# Roland.net
KiCad netlist of a schematic drawn in EAGLE
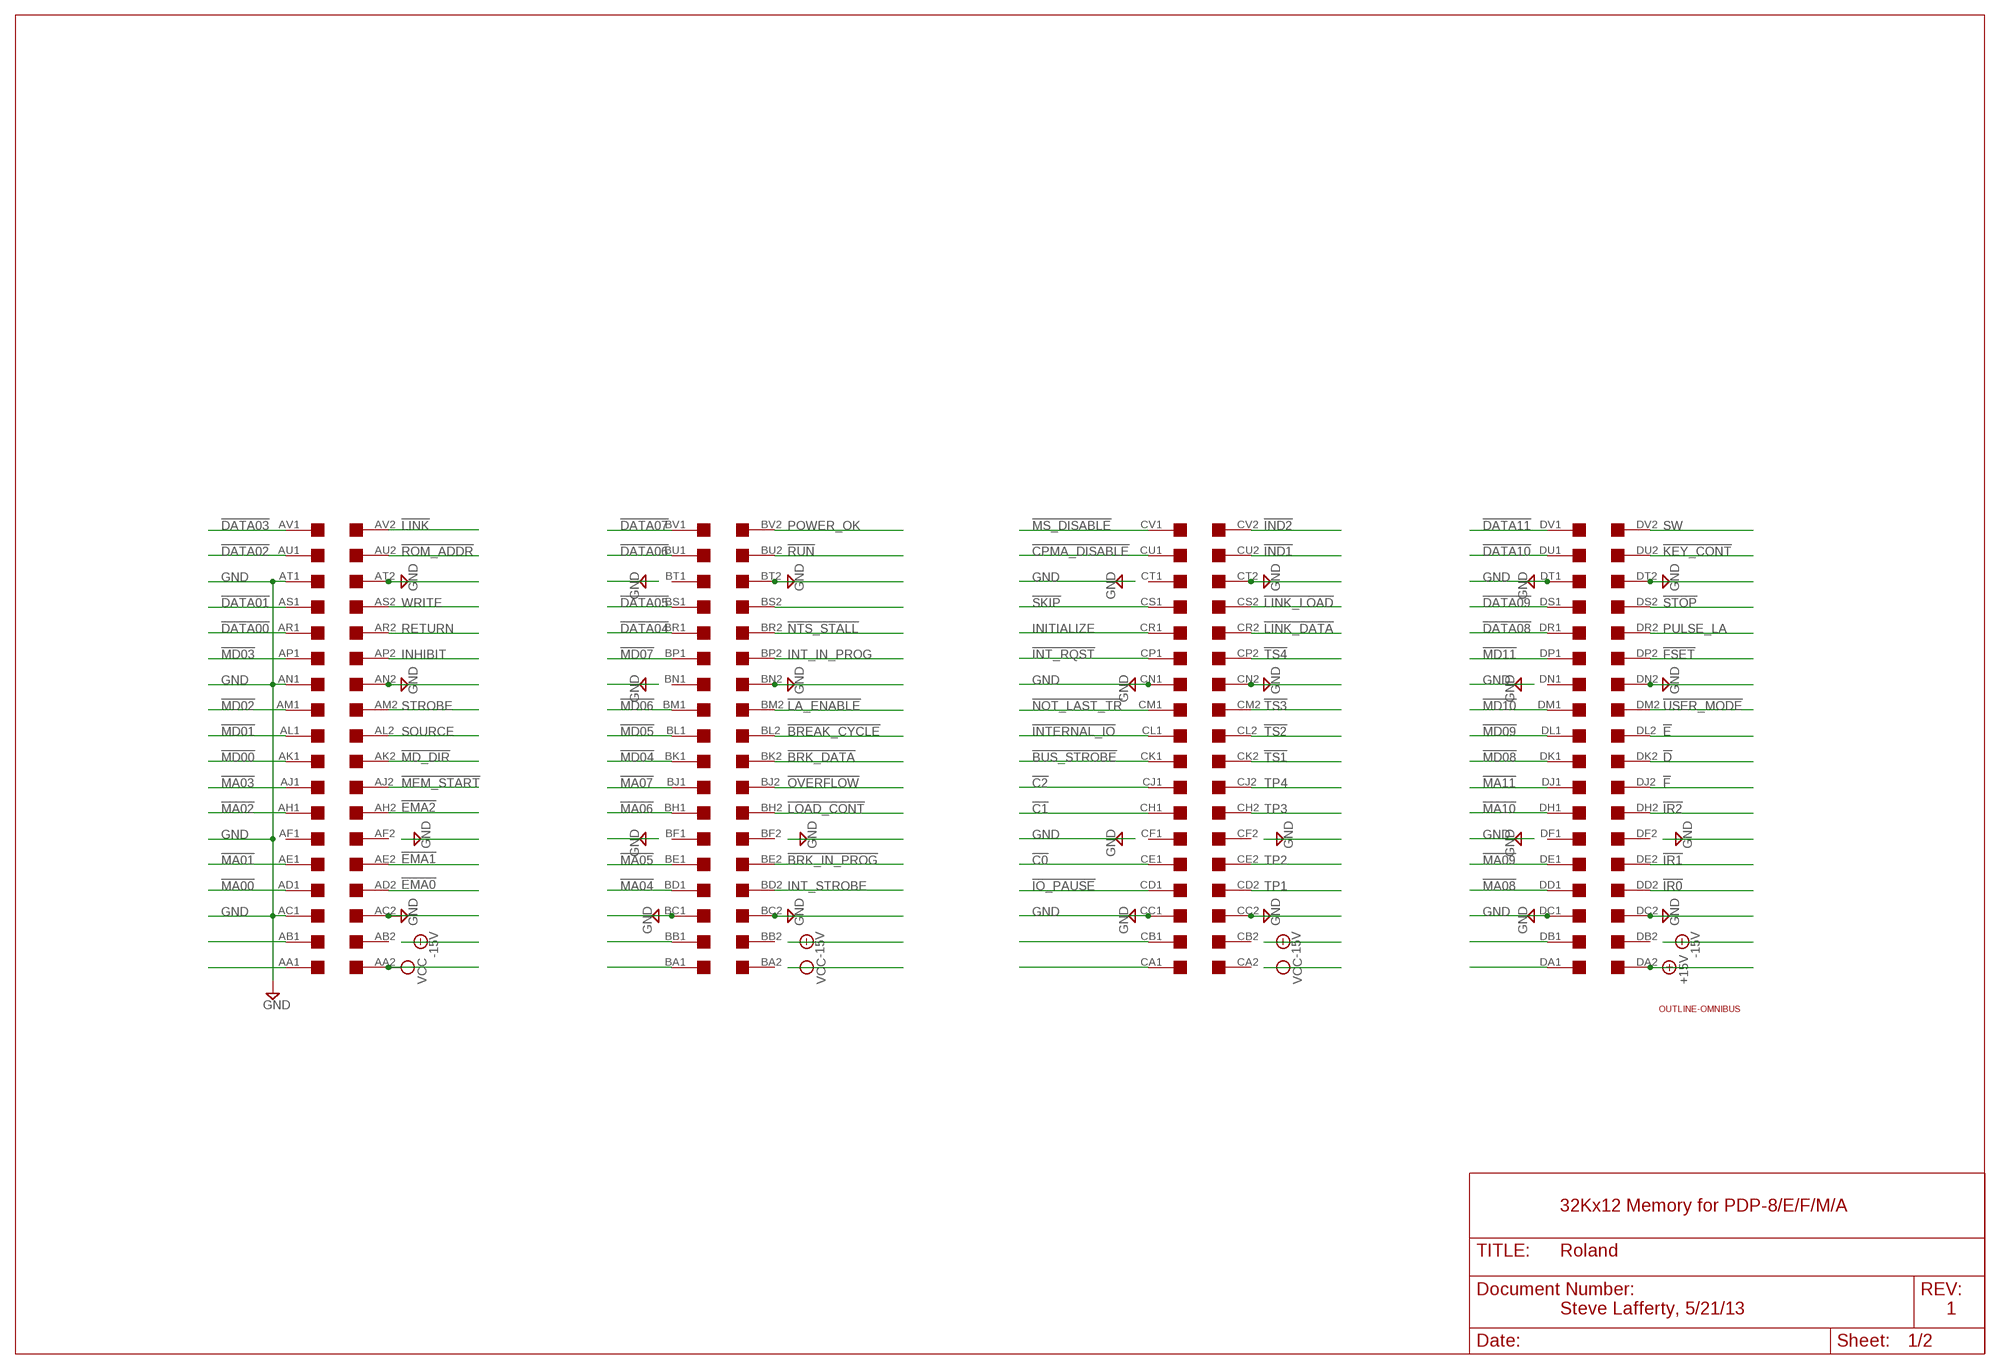
[diagram p0: schematic, sheet 1]
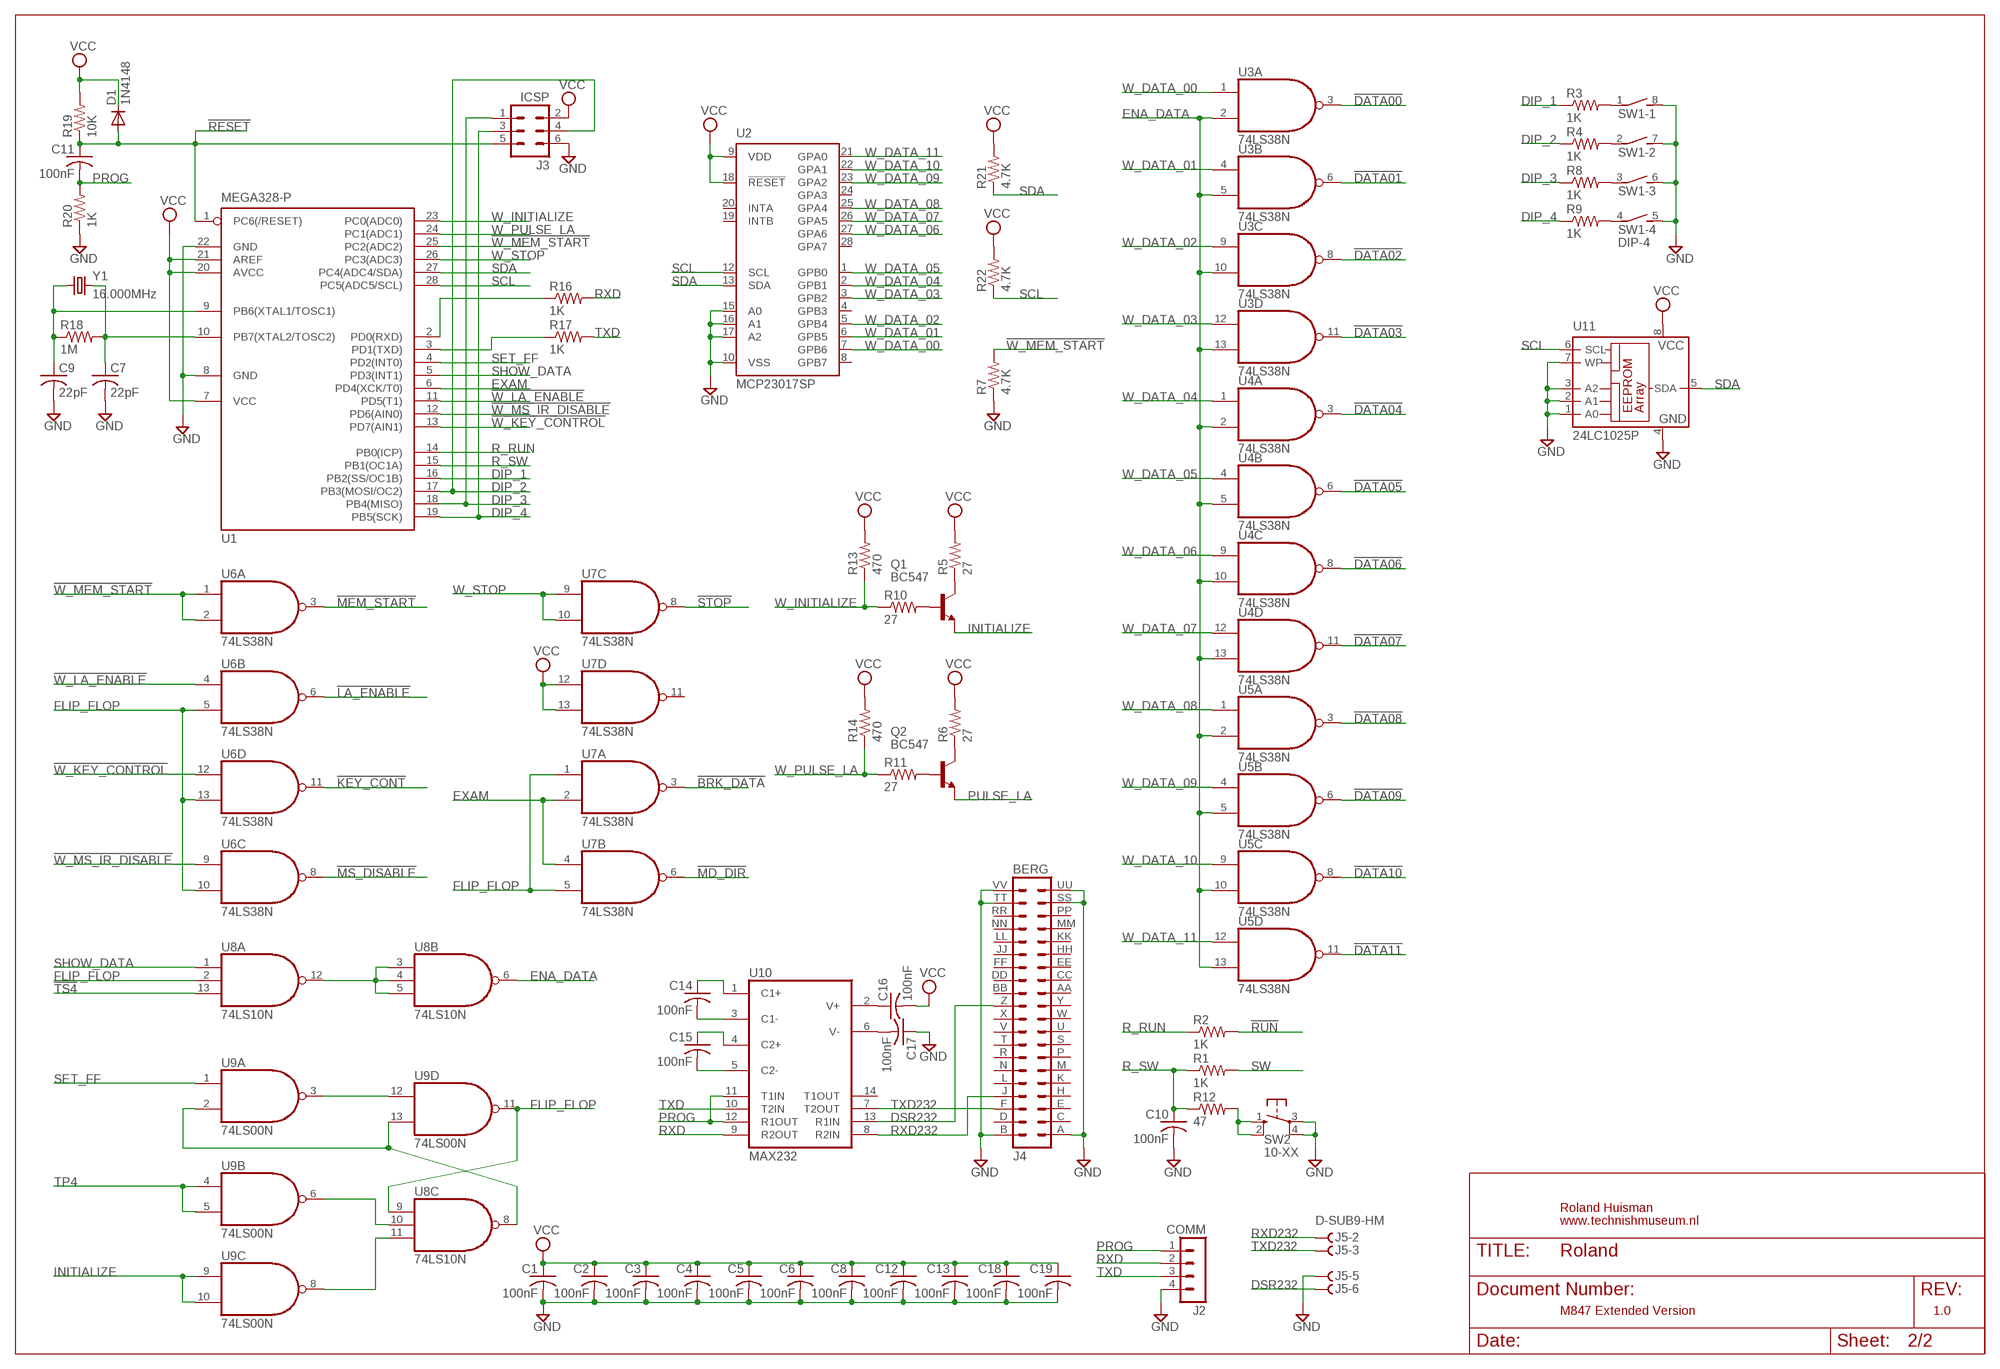
[diagram p1: schematic, sheet 2]

(export (version "E")
  (design (tool "Eeschema 10.0.6"))
  (components
    (comp (ref "J1")
      (value "EDGE")
      (footprint "eagle-import:EDGE-CON8")
      (libsource (lib "eagle-import") (part "QUAD"))
    )
    (comp (ref "U$1")
      (value "OUTLINE-OMNIBUS")
      (footprint "eagle-import:OMNIBUS")
      (libsource (lib "eagle-import") (part "OUTLINE-OMNIBUS"))
    )
    (comp (ref "C1")
      (value "100nF")
      (footprint "eagle-import:C050-025X075")
      (libsource (lib "eagle-import") (part "C-US050-025X075"))
    )
    (comp (ref "C2")
      (value "100nF")
      (footprint "eagle-import:C050-025X075")
      (libsource (lib "eagle-import") (part "C-US050-025X075"))
    )
    (comp (ref "C3")
      (value "100nF")
      (footprint "eagle-import:C050-025X075")
      (libsource (lib "eagle-import") (part "C-US050-025X075"))
    )
    (comp (ref "C4")
      (value "100nF")
      (footprint "eagle-import:C050-025X075")
      (libsource (lib "eagle-import") (part "C-US050-025X075"))
    )
    (comp (ref "C5")
      (value "100nF")
      (footprint "eagle-import:C050-025X075")
      (libsource (lib "eagle-import") (part "C-US050-025X075"))
    )
    (comp (ref "C6")
      (value "100nF")
      (footprint "eagle-import:C050-025X075")
      (libsource (lib "eagle-import") (part "C-US050-025X075"))
    )
    (comp (ref "C7")
      (value "22pF")
      (footprint "eagle-import:C050-025X075")
      (libsource (lib "eagle-import") (part "C-US050-025X075"))
    )
    (comp (ref "C8")
      (value "100nF")
      (footprint "eagle-import:C050-025X075")
      (libsource (lib "eagle-import") (part "C-US050-025X075"))
    )
    (comp (ref "C9")
      (value "22pF")
      (footprint "eagle-import:C050-025X075")
      (libsource (lib "eagle-import") (part "C-US050-025X075"))
    )
    (comp (ref "C10")
      (value "100nF")
      (footprint "eagle-import:C050-025X075")
      (libsource (lib "eagle-import") (part "C-US050-025X075"))
    )
    (comp (ref "C11")
      (value "100nF")
      (footprint "eagle-import:C050-025X075")
      (libsource (lib "eagle-import") (part "C-US050-025X075"))
    )
    (comp (ref "C12")
      (value "100nF")
      (footprint "eagle-import:C050-025X075")
      (libsource (lib "eagle-import") (part "C-US050-025X075"))
    )
    (comp (ref "C13")
      (value "100nF")
      (footprint "eagle-import:C050-025X075")
      (libsource (lib "eagle-import") (part "C-US050-025X075"))
    )
    (comp (ref "C14")
      (value "100nF")
      (footprint "eagle-import:C050-025X075")
      (libsource (lib "eagle-import") (part "C-US050-025X075"))
    )
    (comp (ref "C15")
      (value "100nF")
      (footprint "eagle-import:C050-025X075")
      (libsource (lib "eagle-import") (part "C-US050-025X075"))
    )
    (comp (ref "C16")
      (value "100nF")
      (footprint "eagle-import:C050-025X075")
      (libsource (lib "eagle-import") (part "C-US050-025X075"))
    )
    (comp (ref "C17")
      (value "100nF")
      (footprint "eagle-import:C050-025X075")
      (libsource (lib "eagle-import") (part "C-US050-025X075"))
    )
    (comp (ref "C18")
      (value "100nF")
      (footprint "eagle-import:C050-025X075")
      (libsource (lib "eagle-import") (part "C-US050-025X075"))
    )
    (comp (ref "C19")
      (value "100nF")
      (footprint "eagle-import:C050-025X075")
      (libsource (lib "eagle-import") (part "C-US050-025X075"))
    )
    (comp (ref "D1")
      (value "1N4148")
      (footprint "eagle-import:DO35-10")
      (libsource (lib "eagle-import") (part "1N4148DO35-10"))
    )
    (comp (ref "J2")
      (value "COMM")
      (footprint "eagle-import:MA04-1")
      (libsource (lib "eagle-import") (part "MA04-1"))
    )
    (comp (ref "J3")
      (value "ICSP")
      (footprint "eagle-import:MA03-2")
      (libsource (lib "eagle-import") (part "MA03-2"))
    )
    (comp (ref "J4")
      (value "BERG")
      (footprint "eagle-import:DEC40PINH")
      (libsource (lib "eagle-import") (part "DEC40PINH"))
    )
    (comp (ref "J5")
      (value "D-SUB9-HM")
      (footprint "eagle-import:H5M09RA")
      (libsource (lib "eagle-import") (part "D-SUB9-H5M09RA"))
    )
    (comp (ref "Q1")
      (value "BC547")
      (footprint "eagle-import:TO5")
      (libsource (lib "eagle-import") (part "-NPN-TO5"))
    )
    (comp (ref "Q2")
      (value "BC547")
      (footprint "eagle-import:TO5")
      (libsource (lib "eagle-import") (part "-NPN-TO5"))
    )
    (comp (ref "R1")
      (value "1K")
      (footprint "eagle-import:0207_15")
      (libsource (lib "eagle-import") (part "R-US_0207/15"))
    )
    (comp (ref "R2")
      (value "1K")
      (footprint "eagle-import:0207_15")
      (libsource (lib "eagle-import") (part "R-US_0207/15"))
    )
    (comp (ref "R3")
      (value "1K")
      (footprint "eagle-import:0207_15")
      (libsource (lib "eagle-import") (part "R-US_0207/15"))
    )
    (comp (ref "R4")
      (value "1K")
      (footprint "eagle-import:0207_15")
      (libsource (lib "eagle-import") (part "R-US_0207/15"))
    )
    (comp (ref "R5")
      (value "27")
      (footprint "eagle-import:0207_15")
      (libsource (lib "eagle-import") (part "R-US_0207/15"))
    )
    (comp (ref "R6")
      (value "27")
      (footprint "eagle-import:0207_15")
      (libsource (lib "eagle-import") (part "R-US_0207/15"))
    )
    (comp (ref "R7")
      (value "4.7K")
      (footprint "eagle-import:0207_15")
      (libsource (lib "eagle-import") (part "R-US_0207/15"))
    )
    (comp (ref "R8")
      (value "1K")
      (footprint "eagle-import:0207_15")
      (libsource (lib "eagle-import") (part "R-US_0207/15"))
    )
    (comp (ref "R9")
      (value "1K")
      (footprint "eagle-import:0207_15")
      (libsource (lib "eagle-import") (part "R-US_0207/15"))
    )
    (comp (ref "R10")
      (value "27")
      (footprint "eagle-import:0207_15")
      (libsource (lib "eagle-import") (part "R-US_0207/15"))
    )
    (comp (ref "R11")
      (value "27")
      (footprint "eagle-import:0207_15")
      (libsource (lib "eagle-import") (part "R-US_0207/15"))
    )
    (comp (ref "R12")
      (value "47")
      (footprint "eagle-import:0207_15")
      (libsource (lib "eagle-import") (part "R-US_0207/15"))
    )
    (comp (ref "R13")
      (value "470")
      (footprint "eagle-import:0207_15")
      (libsource (lib "eagle-import") (part "R-US_0207/15"))
    )
    (comp (ref "R14")
      (value "470")
      (footprint "eagle-import:0207_15")
      (libsource (lib "eagle-import") (part "R-US_0207/15"))
    )
    (comp (ref "R16")
      (value "1K")
      (footprint "eagle-import:0207_15")
      (libsource (lib "eagle-import") (part "R-US_0207/15"))
    )
    (comp (ref "R17")
      (value "1K")
      (footprint "eagle-import:0207_15")
      (libsource (lib "eagle-import") (part "R-US_0207/15"))
    )
    (comp (ref "R18")
      (value "1M")
      (footprint "eagle-import:0207_15")
      (libsource (lib "eagle-import") (part "R-US_0207/15"))
    )
    (comp (ref "R19")
      (value "10K")
      (footprint "eagle-import:0207_15")
      (libsource (lib "eagle-import") (part "R-US_0207/15"))
    )
    (comp (ref "R20")
      (value "1K")
      (footprint "eagle-import:0207_15")
      (libsource (lib "eagle-import") (part "R-US_0207/15"))
    )
    (comp (ref "R21")
      (value "4.7K")
      (footprint "eagle-import:0207_15")
      (libsource (lib "eagle-import") (part "R-US_0207/15"))
    )
    (comp (ref "R22")
      (value "4.7K")
      (footprint "eagle-import:0207_15")
      (libsource (lib "eagle-import") (part "R-US_0207/15"))
    )
    (comp (ref "SW1")
      (value "DIP-4")
      (footprint "eagle-import:DIP04S")
      (libsource (lib "eagle-import") (part "DIP04S"))
    )
    (comp (ref "SW2")
      (value "10-XX")
      (footprint "eagle-import:B3F-10XX")
      (fields (field (name "MPN") "B3F-1000"))
      (libsource (lib "eagle-import") (part "10-XX"))
    )
    (comp (ref "U1")
      (value "MEGA328-P")
      (footprint "eagle-import:DIL28-3")
      (libsource (lib "eagle-import") (part "MEGA8-P"))
    )
    (comp (ref "U2")
      (value "MCP23017SP")
      (footprint "eagle-import:DIL28-3")
      (fields (field (name "MF") "MICROCHIP") (field (name "MPN") "MCP23017-E/SP"))
      (libsource (lib "eagle-import") (part "MCP23017SP"))
    )
    (comp (ref "U3")
      (value "74LS38N")
      (footprint "eagle-import:DIL14")
      (libsource (lib "eagle-import") (part "7438NLS"))
    )
    (comp (ref "U4")
      (value "74LS38N")
      (footprint "eagle-import:DIL14")
      (libsource (lib "eagle-import") (part "7438NLS"))
    )
    (comp (ref "U5")
      (value "74LS38N")
      (footprint "eagle-import:DIL14")
      (libsource (lib "eagle-import") (part "7438NLS"))
    )
    (comp (ref "U6")
      (value "74LS38N")
      (footprint "eagle-import:DIL14")
      (libsource (lib "eagle-import") (part "7438NLS"))
    )
    (comp (ref "U7")
      (value "74LS38N")
      (footprint "eagle-import:DIL14")
      (libsource (lib "eagle-import") (part "7438NLS"))
    )
    (comp (ref "U8")
      (value "74LS10N")
      (footprint "eagle-import:DIL14")
      (libsource (lib "eagle-import") (part "7410NLS"))
    )
    (comp (ref "U9")
      (value "74LS00N")
      (footprint "eagle-import:DIL14")
      (libsource (lib "eagle-import") (part "7400NLS"))
    )
    (comp (ref "U10")
      (value "MAX232")
      (footprint "eagle-import:DIL16")
      (fields (field (name "MF") "MAXIM") (field (name "MPN") "MAX232ACPE+"))
      (libsource (lib "eagle-import") (part "MAX232"))
    )
    (comp (ref "U11")
      (value "24LC1025P")
      (footprint "eagle-import:DIL8")
      (fields (field (name "MF") "MICROCHIP") (field (name "MPN") "24LC025-I/P"))
      (libsource (lib "eagle-import") (part "24PLC025"))
    )
    (comp (ref "Y1")
      (value "16.000MHz")
      (footprint "eagle-import:HC49U-H")
      (libsource (lib "eagle-import") (part "CRYSTALHC49U-H"))
    )
  )
  (nets
    (net (code "1") (name "+15V") (class "Default")
      (node (ref "J1") (pin "DA2") (pinfunction "1_DA2") (pintype "bidirectional"))
    )
    (net (code "3") (name "DIP_1") (class "Default")
      (node (ref "R3") (pin "1") (pinfunction "1_1") (pintype "passive"))
      (node (ref "U1") (pin "16") (pinfunction "PB2(SS/OC1B)_16") (pintype "bidirectional"))
    )
    (net (code "4") (name "DIP_2") (class "Default")
      (node (ref "J3") (pin "4") (pinfunction "4_4") (pintype "passive"))
      (node (ref "R4") (pin "1") (pinfunction "1_1") (pintype "passive"))
      (node (ref "U1") (pin "17") (pinfunction "PB3(MOSI/OC2)_17") (pintype "bidirectional"))
    )
    (net (code "5") (name "DIP_3") (class "Default")
      (node (ref "J3") (pin "1") (pinfunction "1_1") (pintype "passive"))
      (node (ref "R8") (pin "1") (pinfunction "1_1") (pintype "passive"))
      (node (ref "U1") (pin "18") (pinfunction "PB4(MISO)_18") (pintype "bidirectional"))
    )
    (net (code "6") (name "DIP_4") (class "Default")
      (node (ref "J3") (pin "3") (pinfunction "3_3") (pintype "passive"))
      (node (ref "R9") (pin "1") (pinfunction "1_1") (pintype "passive"))
      (node (ref "U1") (pin "19") (pinfunction "PB5(SCK)_19") (pintype "bidirectional"))
    )
    (net (code "7") (name "DSR232") (class "Default")
      (node (ref "J4") (pin "Z") (pinfunction "22_Z") (pintype "bidirectional"))
      (node (ref "J5") (pin "6") (pinfunction "F_6") (pintype "passive"))
      (node (ref "U10") (pin "13") (pinfunction "R1IN_13") (pintype "input"))
    )
    (net (code "8") (name "ENA_DATA") (class "Default")
      (node (ref "U3") (pin "10") (pinfunction "I1_10") (pintype "input"))
      (node (ref "U3") (pin "13") (pinfunction "I1_13") (pintype "input"))
      (node (ref "U3") (pin "2") (pinfunction "I1_2") (pintype "input"))
      (node (ref "U3") (pin "5") (pinfunction "I1_5") (pintype "input"))
      (node (ref "U4") (pin "10") (pinfunction "I1_10") (pintype "input"))
      (node (ref "U4") (pin "13") (pinfunction "I1_13") (pintype "input"))
      (node (ref "U4") (pin "2") (pinfunction "I1_2") (pintype "input"))
      (node (ref "U4") (pin "5") (pinfunction "I1_5") (pintype "input"))
      (node (ref "U5") (pin "10") (pinfunction "I1_10") (pintype "input"))
      (node (ref "U5") (pin "13") (pinfunction "I1_13") (pintype "input"))
      (node (ref "U5") (pin "2") (pinfunction "I1_2") (pintype "input"))
      (node (ref "U5") (pin "5") (pinfunction "I1_5") (pintype "input"))
      (node (ref "U8") (pin "6") (pinfunction "O_6") (pintype "output"))
    )
    (net (code "9") (name "EXAM") (class "Default")
      (node (ref "U1") (pin "6") (pinfunction "PD4(XCK/T0)_6") (pintype "bidirectional"))
      (node (ref "U7") (pin "2") (pinfunction "I1_2") (pintype "input"))
      (node (ref "U7") (pin "4") (pinfunction "I0_4") (pintype "input"))
    )
    (net (code "10") (name "FLIP_FLOP") (class "Default")
      (node (ref "U6") (pin "10") (pinfunction "I1_10") (pintype "input"))
      (node (ref "U6") (pin "13") (pinfunction "I1_13") (pintype "input"))
      (node (ref "U6") (pin "5") (pinfunction "I1_5") (pintype "input"))
      (node (ref "U7") (pin "1") (pinfunction "I0_1") (pintype "input"))
      (node (ref "U7") (pin "5") (pinfunction "I1_5") (pintype "input"))
      (node (ref "U8") (pin "2") (pinfunction "I1_2") (pintype "input"))
      (node (ref "U8") (pin "9") (pinfunction "I0_9") (pintype "input"))
      (node (ref "U9") (pin "11") (pinfunction "O_11") (pintype "output"))
    )
    (net (code "11") (name "GND") (class "Default")
      (node (ref "C1") (pin "2") (pinfunction "2_2") (pintype "passive"))
      (node (ref "C10") (pin "2") (pinfunction "2_2") (pintype "passive"))
      (node (ref "C12") (pin "2") (pinfunction "2_2") (pintype "passive"))
      (node (ref "C13") (pin "2") (pinfunction "2_2") (pintype "passive"))
      (node (ref "C17") (pin "1") (pinfunction "1_1") (pintype "passive"))
      (node (ref "C18") (pin "2") (pinfunction "2_2") (pintype "passive"))
      (node (ref "C19") (pin "2") (pinfunction "2_2") (pintype "passive"))
      (node (ref "C2") (pin "2") (pinfunction "2_2") (pintype "passive"))
      (node (ref "C3") (pin "2") (pinfunction "2_2") (pintype "passive"))
      (node (ref "C4") (pin "2") (pinfunction "2_2") (pintype "passive"))
      (node (ref "C5") (pin "2") (pinfunction "2_2") (pintype "passive"))
      (node (ref "C6") (pin "2") (pinfunction "2_2") (pintype "passive"))
      (node (ref "C7") (pin "2") (pinfunction "2_2") (pintype "passive"))
      (node (ref "C8") (pin "2") (pinfunction "2_2") (pintype "passive"))
      (node (ref "C9") (pin "2") (pinfunction "2_2") (pintype "passive"))
      (node (ref "J1") (pin "AC1") (pinfunction "1_AC1") (pintype "bidirectional"))
      (node (ref "J1") (pin "AC2") (pinfunction "1_AC2") (pintype "bidirectional"))
      (node (ref "J1") (pin "AN1") (pinfunction "1_AN1") (pintype "bidirectional"))
      (node (ref "J1") (pin "AN2") (pinfunction "1_AN2") (pintype "bidirectional"))
      (node (ref "J1") (pin "AT1") (pinfunction "1_AT1") (pintype "bidirectional"))
      (node (ref "J1") (pin "AT2") (pinfunction "1_AT2") (pintype "bidirectional"))
      (node (ref "J1") (pin "BC1") (pinfunction "1_BC1") (pintype "bidirectional"))
      (node (ref "J1") (pin "BC2") (pinfunction "1_BC2") (pintype "bidirectional"))
      (node (ref "J1") (pin "BN2") (pinfunction "1_BN2") (pintype "bidirectional"))
      (node (ref "J1") (pin "BT2") (pinfunction "1_BT2") (pintype "bidirectional"))
      (node (ref "J1") (pin "CC1") (pinfunction "1_CC1") (pintype "bidirectional"))
      (node (ref "J1") (pin "CC2") (pinfunction "1_CC2") (pintype "bidirectional"))
      (node (ref "J1") (pin "CN1") (pinfunction "1_CN1") (pintype "bidirectional"))
      (node (ref "J1") (pin "CN2") (pinfunction "1_CN2") (pintype "bidirectional"))
      (node (ref "J1") (pin "CT2") (pinfunction "1_CT2") (pintype "bidirectional"))
      (node (ref "J1") (pin "DC1") (pinfunction "1_DC1") (pintype "bidirectional"))
      (node (ref "J1") (pin "DC2") (pinfunction "1_DC2") (pintype "bidirectional"))
      (node (ref "J1") (pin "DN2") (pinfunction "1_DN2") (pintype "bidirectional"))
      (node (ref "J1") (pin "DT1") (pinfunction "1_DT1") (pintype "bidirectional"))
      (node (ref "J1") (pin "DT2") (pinfunction "1_DT2") (pintype "bidirectional"))
      (node (ref "J2") (pin "4") (pinfunction "4_4") (pintype "passive"))
      (node (ref "J3") (pin "6") (pinfunction "6_6") (pintype "passive"))
      (node (ref "J4") (pin "A") (pinfunction "1_A") (pintype "bidirectional"))
      (node (ref "J4") (pin "B") (pinfunction "2_B") (pintype "bidirectional"))
      (node (ref "J4") (pin "SS") (pinfunction "37_SS") (pintype "bidirectional"))
      (node (ref "J4") (pin "TT") (pinfunction "38_TT") (pintype "bidirectional"))
      (node (ref "J4") (pin "UU") (pinfunction "39_UU") (pintype "bidirectional"))
      (node (ref "J4") (pin "VV") (pinfunction "40_VV") (pintype "bidirectional"))
      (node (ref "J5") (pin "5") (pinfunction "F_5") (pintype "passive"))
      (node (ref "R20") (pin "1") (pinfunction "1_1") (pintype "passive"))
      (node (ref "R7") (pin "1") (pinfunction "1_1") (pintype "passive"))
      (node (ref "SW1") (pin "5") (pinfunction "2_5") (pintype "passive"))
      (node (ref "SW1") (pin "6") (pinfunction "2_6") (pintype "passive"))
      (node (ref "SW1") (pin "7") (pinfunction "2_7") (pintype "passive"))
      (node (ref "SW1") (pin "8") (pinfunction "2_8") (pintype "passive"))
      (node (ref "SW2") (pin "3") (pinfunction "P_3") (pintype "passive"))
      (node (ref "SW2") (pin "4") (pinfunction "P1_4") (pintype "passive"))
      (node (ref "U1") (pin "22") (pinfunction "GND_22") (pintype "power_in"))
      (node (ref "U1") (pin "8") (pinfunction "GND_8") (pintype "power_in"))
      (node (ref "U11") (pin "1") (pinfunction "A0_1") (pintype "input"))
      (node (ref "U11") (pin "2") (pinfunction "A1_2") (pintype "input"))
      (node (ref "U11") (pin "3") (pinfunction "A2_3") (pintype "input"))
      (node (ref "U11") (pin "4") (pinfunction "GND_4") (pintype "power_in"))
      (node (ref "U11") (pin "7") (pinfunction "WP_7") (pintype "input"))
      (node (ref "U2") (pin "10") (pinfunction "VSS_10") (pintype "power_in"))
      (node (ref "U2") (pin "15") (pinfunction "A0_15") (pintype "input"))
      (node (ref "U2") (pin "16") (pinfunction "A1_16") (pintype "input"))
      (node (ref "U2") (pin "17") (pinfunction "A2_17") (pintype "input"))
    )
    (net (code "12") (name "INHIBIT") (class "Default")
      (node (ref "J1") (pin "AP2") (pinfunction "1_AP2") (pintype "bidirectional"))
    )
    (net (code "13") (name "INITIALIZE") (class "Default")
      (node (ref "J1") (pin "CR1") (pinfunction "1_CR1") (pintype "bidirectional"))
      (node (ref "Q1") (pin "1") (pinfunction "E_1") (pintype "passive"))
      (node (ref "U9") (pin "10") (pinfunction "I1_10") (pintype "input"))
      (node (ref "U9") (pin "9") (pinfunction "I0_9") (pintype "input"))
    )
    (net (code "14") (name "INT_IN_PROG") (class "Default")
      (node (ref "J1") (pin "BP2") (pinfunction "1_BP2") (pintype "bidirectional"))
    )
    (net (code "15") (name "INT_STROBE") (class "Default")
      (node (ref "J1") (pin "BD2") (pinfunction "1_BD2") (pintype "bidirectional"))
    )
    (net (code "16") (name "Net-(Q1-B)") (class "Default")
      (node (ref "Q1") (pin "2") (pinfunction "B_2") (pintype "passive"))
      (node (ref "R10") (pin "2") (pinfunction "2_2") (pintype "passive"))
    )
    (net (code "17") (name "Net-(Q1-C)") (class "Default")
      (node (ref "Q1") (pin "3") (pinfunction "C_3") (pintype "passive"))
      (node (ref "R5") (pin "1") (pinfunction "1_1") (pintype "passive"))
    )
    (net (code "18") (name "Net-(Q2-B)") (class "Default")
      (node (ref "Q2") (pin "2") (pinfunction "B_2") (pintype "passive"))
      (node (ref "R11") (pin "2") (pinfunction "2_2") (pintype "passive"))
    )
    (net (code "19") (name "Net-(Q2-C)") (class "Default")
      (node (ref "Q2") (pin "3") (pinfunction "C_3") (pintype "passive"))
      (node (ref "R6") (pin "1") (pinfunction "1_1") (pintype "passive"))
    )
    (net (code "20") (name "Net-(R3-Pad2)") (class "Default")
      (node (ref "R3") (pin "2") (pinfunction "2_2") (pintype "passive"))
      (node (ref "SW1") (pin "1") (pinfunction "1_1") (pintype "passive"))
    )
    (net (code "21") (name "Net-(SW1B-1)") (class "Default")
      (node (ref "R4") (pin "2") (pinfunction "2_2") (pintype "passive"))
      (node (ref "SW1") (pin "2") (pinfunction "1_2") (pintype "passive"))
    )
    (net (code "22") (name "Net-(SW1C-1)") (class "Default")
      (node (ref "R8") (pin "2") (pinfunction "2_2") (pintype "passive"))
      (node (ref "SW1") (pin "3") (pinfunction "1_3") (pintype "passive"))
    )
    (net (code "23") (name "Net-(SW1D-1)") (class "Default")
      (node (ref "R9") (pin "2") (pinfunction "2_2") (pintype "passive"))
      (node (ref "SW1") (pin "4") (pinfunction "1_4") (pintype "passive"))
    )
    (net (code "24") (name "Net-(SW2-S)") (class "Default")
      (node (ref "R12") (pin "2") (pinfunction "2_2") (pintype "passive"))
      (node (ref "SW2") (pin "1") (pinfunction "S_1") (pintype "passive"))
      (node (ref "SW2") (pin "2") (pinfunction "S1_2") (pintype "passive"))
    )
    (net (code "25") (name "Net-(U1-PB6(XTAL1{slash}TOSC1))") (class "Default")
      (node (ref "C9") (pin "1") (pinfunction "1_1") (pintype "passive"))
      (node (ref "R18") (pin "1") (pinfunction "1_1") (pintype "passive"))
      (node (ref "U1") (pin "9") (pinfunction "PB6(XTAL1/TOSC1)_9") (pintype "bidirectional"))
      (node (ref "Y1") (pin "2") (pinfunction "2_2") (pintype "passive"))
    )
    (net (code "26") (name "Net-(U1-PB7(XTAL2{slash}TOSC2))") (class "Default")
      (node (ref "C7") (pin "1") (pinfunction "1_1") (pintype "passive"))
      (node (ref "R18") (pin "2") (pinfunction "2_2") (pintype "passive"))
      (node (ref "U1") (pin "10") (pinfunction "PB7(XTAL2/TOSC2)_10") (pintype "bidirectional"))
      (node (ref "Y1") (pin "1") (pinfunction "1_1") (pintype "passive"))
    )
    (net (code "27") (name "Net-(U1-PD0(RXD))") (class "Default")
      (node (ref "R16") (pin "1") (pinfunction "1_1") (pintype "passive"))
      (node (ref "U1") (pin "2") (pinfunction "PD0(RXD)_2") (pintype "bidirectional"))
    )
    (net (code "28") (name "Net-(U1-PD1(TXD))") (class "Default")
      (node (ref "R17") (pin "1") (pinfunction "1_1") (pintype "passive"))
      (node (ref "U1") (pin "3") (pinfunction "PD1(TXD)_3") (pintype "bidirectional"))
    )
    (net (code "29") (name "Net-(U8A-O)") (class "Default")
      (node (ref "U8") (pin "12") (pinfunction "O_12") (pintype "output"))
      (node (ref "U8") (pin "3") (pinfunction "I0_3") (pintype "input"))
      (node (ref "U8") (pin "4") (pinfunction "I1_4") (pintype "input"))
      (node (ref "U8") (pin "5") (pinfunction "I2_5") (pintype "input"))
    )
    (net (code "30") (name "Net-(U8C-I1)") (class "Default")
      (node (ref "U8") (pin "10") (pinfunction "I1_10") (pintype "input"))
      (node (ref "U9") (pin "6") (pinfunction "O_6") (pintype "output"))
    )
    (net (code "31") (name "Net-(U8C-I2)") (class "Default")
      (node (ref "U8") (pin "11") (pinfunction "I2_11") (pintype "input"))
      (node (ref "U9") (pin "8") (pinfunction "O_8") (pintype "output"))
    )
    (net (code "32") (name "Net-(U8C-O)") (class "Default")
      (node (ref "U8") (pin "8") (pinfunction "O_8") (pintype "output"))
      (node (ref "U9") (pin "13") (pinfunction "I1_13") (pintype "input"))
      (node (ref "U9") (pin "2") (pinfunction "I1_2") (pintype "input"))
    )
    (net (code "33") (name "Net-(U9A-O)") (class "Default")
      (node (ref "U9") (pin "12") (pinfunction "I0_12") (pintype "input"))
      (node (ref "U9") (pin "3") (pinfunction "O_3") (pintype "output"))
    )
    (net (code "34") (name "Net-(U10A-C1+)") (class "Default")
      (node (ref "C14") (pin "1") (pinfunction "1_1") (pintype "passive"))
      (node (ref "U10") (pin "1") (pinfunction "C1+_1") (pintype "bidirectional"))
    )
    (net (code "35") (name "Net-(U10A-C1-)") (class "Default")
      (node (ref "C14") (pin "2") (pinfunction "2_2") (pintype "passive"))
      (node (ref "U10") (pin "3") (pinfunction "C1-_3") (pintype "bidirectional"))
    )
    (net (code "36") (name "Net-(U10A-C2+)") (class "Default")
      (node (ref "C15") (pin "1") (pinfunction "1_1") (pintype "passive"))
      (node (ref "U10") (pin "4") (pinfunction "C2+_4") (pintype "bidirectional"))
    )
    (net (code "37") (name "Net-(U10A-C2-)") (class "Default")
      (node (ref "C15") (pin "2") (pinfunction "2_2") (pintype "passive"))
      (node (ref "U10") (pin "5") (pinfunction "C2-_5") (pintype "bidirectional"))
    )
    (net (code "38") (name "Net-(U10A-V+)") (class "Default")
      (node (ref "C16") (pin "1") (pinfunction "1_1") (pintype "passive"))
      (node (ref "U10") (pin "2") (pinfunction "V+_2") (pintype "bidirectional"))
    )
    (net (code "39") (name "Net-(U10A-V-)") (class "Default")
      (node (ref "C17") (pin "2") (pinfunction "2_2") (pintype "passive"))
      (node (ref "U10") (pin "6") (pinfunction "V-_6") (pintype "bidirectional"))
    )
    (net (code "40") (name "POWER_OK") (class "Default")
      (node (ref "J1") (pin "BV2") (pinfunction "1_BV2") (pintype "bidirectional"))
    )
    (net (code "41") (name "PROG") (class "Default")
      (node (ref "C11") (pin "2") (pinfunction "2_2") (pintype "passive"))
      (node (ref "J2") (pin "1") (pinfunction "1_1") (pintype "passive"))
      (node (ref "R20") (pin "2") (pinfunction "2_2") (pintype "passive"))
      (node (ref "U10") (pin "11") (pinfunction "T1IN_11") (pintype "input"))
      (node (ref "U10") (pin "12") (pinfunction "R1OUT_12") (pintype "output"))
    )
    (net (code "42") (name "PULSE_LA") (class "Default")
      (node (ref "J1") (pin "DR2") (pinfunction "1_DR2") (pintype "bidirectional"))
      (node (ref "Q2") (pin "1") (pinfunction "E_1") (pintype "passive"))
    )
    (net (code "43") (name "RETURN") (class "Default")
      (node (ref "J1") (pin "AR2") (pinfunction "1_AR2") (pintype "bidirectional"))
    )
    (net (code "44") (name "RXD") (class "Default")
      (node (ref "J2") (pin "2") (pinfunction "2_2") (pintype "passive"))
      (node (ref "R16") (pin "2") (pinfunction "2_2") (pintype "passive"))
      (node (ref "U10") (pin "9") (pinfunction "R2OUT_9") (pintype "output"))
    )
    (net (code "45") (name "RXD232") (class "Default")
      (node (ref "J4") (pin "J") (pinfunction "8_J") (pintype "bidirectional"))
      (node (ref "J5") (pin "2") (pinfunction "F_2") (pintype "passive"))
      (node (ref "U10") (pin "8") (pinfunction "R2IN_8") (pintype "input"))
    )
    (net (code "46") (name "R_RUN") (class "Default")
      (node (ref "R2") (pin "1") (pinfunction "1_1") (pintype "passive"))
      (node (ref "U1") (pin "14") (pinfunction "PB0(ICP)_14") (pintype "bidirectional"))
    )
    (net (code "47") (name "R_SW") (class "Default")
      (node (ref "C10") (pin "1") (pinfunction "1_1") (pintype "passive"))
      (node (ref "R1") (pin "1") (pinfunction "1_1") (pintype "passive"))
      (node (ref "R12") (pin "1") (pinfunction "1_1") (pintype "passive"))
      (node (ref "U1") (pin "15") (pinfunction "PB1(OC1A)_15") (pintype "bidirectional"))
    )
    (net (code "48") (name "SCL") (class "Default")
      (node (ref "R22") (pin "1") (pinfunction "1_1") (pintype "passive"))
      (node (ref "U1") (pin "28") (pinfunction "PC5(ADC5/SCL)_28") (pintype "bidirectional"))
      (node (ref "U11") (pin "6") (pinfunction "SCL_6") (pintype "input"))
      (node (ref "U2") (pin "12") (pinfunction "SCL_12") (pintype "input"))
    )
    (net (code "49") (name "SDA") (class "Default")
      (node (ref "R21") (pin "1") (pinfunction "1_1") (pintype "passive"))
      (node (ref "U1") (pin "27") (pinfunction "PC4(ADC4/SDA)_27") (pintype "bidirectional"))
      (node (ref "U11") (pin "5") (pinfunction "SDA_5") (pintype "bidirectional"))
      (node (ref "U2") (pin "13") (pinfunction "SDA_13") (pintype "bidirectional"))
    )
    (net (code "50") (name "SET_FF") (class "Default")
      (node (ref "U1") (pin "4") (pinfunction "PD2(INT0)_4") (pintype "bidirectional"))
      (node (ref "U9") (pin "1") (pinfunction "I0_1") (pintype "input"))
    )
    (net (code "51") (name "SHOW_DATA") (class "Default")
      (node (ref "U1") (pin "5") (pinfunction "PD3(INT1)_5") (pintype "bidirectional"))
      (node (ref "U8") (pin "1") (pinfunction "I0_1") (pintype "input"))
    )
    (net (code "52") (name "SOURCE") (class "Default")
      (node (ref "J1") (pin "AL2") (pinfunction "1_AL2") (pintype "bidirectional"))
    )
    (net (code "53") (name "STROBE") (class "Default")
      (node (ref "J1") (pin "AM2") (pinfunction "1_AM2") (pintype "bidirectional"))
    )
    (net (code "54") (name "SW") (class "Default")
      (node (ref "J1") (pin "DV2") (pinfunction "1_DV2") (pintype "bidirectional"))
      (node (ref "R1") (pin "2") (pinfunction "2_2") (pintype "passive"))
    )
    (net (code "55") (name "TP1") (class "Default")
      (node (ref "J1") (pin "CD2") (pinfunction "1_CD2") (pintype "bidirectional"))
    )
    (net (code "56") (name "TP2") (class "Default")
      (node (ref "J1") (pin "CE2") (pinfunction "1_CE2") (pintype "bidirectional"))
    )
    (net (code "57") (name "TP3") (class "Default")
      (node (ref "J1") (pin "CH2") (pinfunction "1_CH2") (pintype "bidirectional"))
    )
    (net (code "58") (name "TP4") (class "Default")
      (node (ref "J1") (pin "CJ2") (pinfunction "1_CJ2") (pintype "bidirectional"))
      (node (ref "U9") (pin "4") (pinfunction "I0_4") (pintype "input"))
      (node (ref "U9") (pin "5") (pinfunction "I1_5") (pintype "input"))
    )
    (net (code "59") (name "TXD") (class "Default")
      (node (ref "J2") (pin "3") (pinfunction "3_3") (pintype "passive"))
      (node (ref "R17") (pin "2") (pinfunction "2_2") (pintype "passive"))
      (node (ref "U10") (pin "10") (pinfunction "T2IN_10") (pintype "input"))
    )
    (net (code "60") (name "TXD232") (class "Default")
      (node (ref "J4") (pin "F") (pinfunction "6_F") (pintype "bidirectional"))
      (node (ref "J5") (pin "3") (pinfunction "F_3") (pintype "passive"))
      (node (ref "U10") (pin "7") (pinfunction "T2OUT_7") (pintype "output"))
    )
    (net (code "61") (name "VCC") (class "Default")
      (node (ref "C1") (pin "1") (pinfunction "1_1") (pintype "passive"))
      (node (ref "C12") (pin "1") (pinfunction "1_1") (pintype "passive"))
      (node (ref "C13") (pin "1") (pinfunction "1_1") (pintype "passive"))
      (node (ref "C16") (pin "2") (pinfunction "2_2") (pintype "passive"))
      (node (ref "C18") (pin "1") (pinfunction "1_1") (pintype "passive"))
      (node (ref "C19") (pin "1") (pinfunction "1_1") (pintype "passive"))
      (node (ref "C2") (pin "1") (pinfunction "1_1") (pintype "passive"))
      (node (ref "C3") (pin "1") (pinfunction "1_1") (pintype "passive"))
      (node (ref "C4") (pin "1") (pinfunction "1_1") (pintype "passive"))
      (node (ref "C5") (pin "1") (pinfunction "1_1") (pintype "passive"))
      (node (ref "C6") (pin "1") (pinfunction "1_1") (pintype "passive"))
      (node (ref "C8") (pin "1") (pinfunction "1_1") (pintype "passive"))
      (node (ref "D1") (pin "C") (pinfunction "C_C") (pintype "passive"))
      (node (ref "J1") (pin "AA2") (pinfunction "1_AA2") (pintype "bidirectional"))
      (node (ref "J3") (pin "2") (pinfunction "2_2") (pintype "passive"))
      (node (ref "R13") (pin "2") (pinfunction "2_2") (pintype "passive"))
      (node (ref "R14") (pin "2") (pinfunction "2_2") (pintype "passive"))
      (node (ref "R19") (pin "2") (pinfunction "2_2") (pintype "passive"))
      (node (ref "R21") (pin "2") (pinfunction "2_2") (pintype "passive"))
      (node (ref "R22") (pin "2") (pinfunction "2_2") (pintype "passive"))
      (node (ref "R5") (pin "2") (pinfunction "2_2") (pintype "passive"))
      (node (ref "R6") (pin "2") (pinfunction "2_2") (pintype "passive"))
      (node (ref "U1") (pin "20") (pinfunction "AVCC_20") (pintype "power_in"))
      (node (ref "U1") (pin "21") (pinfunction "AREF_21") (pintype "passive"))
      (node (ref "U1") (pin "7") (pinfunction "VCC_7") (pintype "power_in"))
      (node (ref "U11") (pin "8") (pinfunction "VCC_8") (pintype "power_in"))
      (node (ref "U2") (pin "18") (pinfunction "~{RESET}_18") (pintype "input"))
      (node (ref "U2") (pin "9") (pinfunction "VDD_9") (pintype "power_in"))
      (node (ref "U7") (pin "12") (pinfunction "I0_12") (pintype "input"))
      (node (ref "U7") (pin "13") (pinfunction "I1_13") (pintype "input"))
    )
    (net (code "62") (name "WRITE") (class "Default")
      (node (ref "J1") (pin "AS2") (pinfunction "1_AS2") (pintype "bidirectional"))
    )
    (net (code "63") (name "W_DATA_00") (class "Default")
      (node (ref "U2") (pin "7") (pinfunction "GPB6_7") (pintype "bidirectional"))
      (node (ref "U3") (pin "1") (pinfunction "I0_1") (pintype "input"))
    )
    (net (code "64") (name "W_DATA_01") (class "Default")
      (node (ref "U2") (pin "6") (pinfunction "GPB5_6") (pintype "bidirectional"))
      (node (ref "U3") (pin "4") (pinfunction "I0_4") (pintype "input"))
    )
    (net (code "65") (name "W_DATA_02") (class "Default")
      (node (ref "U2") (pin "5") (pinfunction "GPB4_5") (pintype "bidirectional"))
      (node (ref "U3") (pin "9") (pinfunction "I0_9") (pintype "input"))
    )
    (net (code "66") (name "W_DATA_03") (class "Default")
      (node (ref "U2") (pin "3") (pinfunction "GPB2_3") (pintype "bidirectional"))
      (node (ref "U3") (pin "12") (pinfunction "I0_12") (pintype "input"))
    )
    (net (code "67") (name "W_DATA_04") (class "Default")
      (node (ref "U2") (pin "2") (pinfunction "GPB1_2") (pintype "bidirectional"))
      (node (ref "U4") (pin "1") (pinfunction "I0_1") (pintype "input"))
    )
    (net (code "68") (name "W_DATA_05") (class "Default")
      (node (ref "U2") (pin "1") (pinfunction "GPB0_1") (pintype "bidirectional"))
      (node (ref "U4") (pin "4") (pinfunction "I0_4") (pintype "input"))
    )
    (net (code "69") (name "W_DATA_06") (class "Default")
      (node (ref "U2") (pin "27") (pinfunction "GPA6_27") (pintype "bidirectional"))
      (node (ref "U4") (pin "9") (pinfunction "I0_9") (pintype "input"))
    )
    (net (code "70") (name "W_DATA_07") (class "Default")
      (node (ref "U2") (pin "26") (pinfunction "GPA5_26") (pintype "bidirectional"))
      (node (ref "U4") (pin "12") (pinfunction "I0_12") (pintype "input"))
    )
    (net (code "71") (name "W_DATA_08") (class "Default")
      (node (ref "U2") (pin "25") (pinfunction "GPA4_25") (pintype "bidirectional"))
      (node (ref "U5") (pin "1") (pinfunction "I0_1") (pintype "input"))
    )
    (net (code "72") (name "W_DATA_09") (class "Default")
      (node (ref "U2") (pin "23") (pinfunction "GPA2_23") (pintype "bidirectional"))
      (node (ref "U5") (pin "4") (pinfunction "I0_4") (pintype "input"))
    )
    (net (code "73") (name "W_DATA_10") (class "Default")
      (node (ref "U2") (pin "22") (pinfunction "GPA1_22") (pintype "bidirectional"))
      (node (ref "U5") (pin "9") (pinfunction "I0_9") (pintype "input"))
    )
    (net (code "74") (name "W_DATA_11") (class "Default")
      (node (ref "U2") (pin "21") (pinfunction "GPA0_21") (pintype "bidirectional"))
      (node (ref "U5") (pin "12") (pinfunction "I0_12") (pintype "input"))
    )
    (net (code "75") (name "W_INITIALIZE") (class "Default")
      (node (ref "R10") (pin "1") (pinfunction "1_1") (pintype "passive"))
      (node (ref "R13") (pin "1") (pinfunction "1_1") (pintype "passive"))
      (node (ref "U1") (pin "23") (pinfunction "PC0(ADC0)_23") (pintype "bidirectional"))
    )
    (net (code "76") (name "W_PULSE_LA") (class "Default")
      (node (ref "R11") (pin "1") (pinfunction "1_1") (pintype "passive"))
      (node (ref "R14") (pin "1") (pinfunction "1_1") (pintype "passive"))
      (node (ref "U1") (pin "24") (pinfunction "PC1(ADC1)_24") (pintype "bidirectional"))
    )
    (net (code "77") (name "W_STOP") (class "Default")
      (node (ref "U1") (pin "26") (pinfunction "PC3(ADC3)_26") (pintype "bidirectional"))
      (node (ref "U7") (pin "10") (pinfunction "I1_10") (pintype "input"))
      (node (ref "U7") (pin "9") (pinfunction "I0_9") (pintype "input"))
    )
    (net (code "78") (name "unconnected-(J1A-1-PadAA1)") (class "Default")
      (node (ref "J1") (pin "AA1") (pinfunction "1_AA1") (pintype "bidirectional"))
    )
    (net (code "79") (name "unconnected-(J1AK-1-PadBA1)") (class "Default")
      (node (ref "J1") (pin "BA1") (pinfunction "1_BA1") (pintype "bidirectional"))
    )
    (net (code "80") (name "unconnected-(J1AL-1-PadBA2)") (class "Default")
      (node (ref "J1") (pin "BA2") (pinfunction "1_BA2") (pintype "bidirectional"))
    )
    (net (code "81") (name "unconnected-(J1AM-1-PadBB1)") (class "Default")
      (node (ref "J1") (pin "BB1") (pinfunction "1_BB1") (pintype "bidirectional"))
    )
    (net (code "82") (name "unconnected-(J1AN-1-PadBB2)") (class "Default")
      (node (ref "J1") (pin "BB2") (pinfunction "1_BB2") (pintype "bidirectional"))
    )
    (net (code "83") (name "unconnected-(J1AU-1-PadBF1)") (class "Default")
      (node (ref "J1") (pin "BF1") (pinfunction "1_BF1") (pintype "bidirectional"))
    )
    (net (code "84") (name "unconnected-(J1AV-1-PadBF2)") (class "Default")
      (node (ref "J1") (pin "BF2") (pinfunction "1_BF2") (pintype "bidirectional"))
    )
    (net (code "85") (name "unconnected-(J1BG-1-PadBN1)") (class "Default")
      (node (ref "J1") (pin "BN1") (pinfunction "1_BN1") (pintype "bidirectional"))
    )
    (net (code "86") (name "unconnected-(J1BN-1-PadBS2)") (class "Default")
      (node (ref "J1") (pin "BS2") (pinfunction "1_BS2") (pintype "bidirectional"))
    )
    (net (code "87") (name "unconnected-(J1BO-1-PadBT1)") (class "Default")
      (node (ref "J1") (pin "BT1") (pinfunction "1_BT1") (pintype "bidirectional"))
    )
    (net (code "88") (name "unconnected-(J1BU-1-PadCA1)") (class "Default")
      (node (ref "J1") (pin "CA1") (pinfunction "1_CA1") (pintype "bidirectional"))
    )
    (net (code "89") (name "unconnected-(J1BV-1-PadCA2)") (class "Default")
      (node (ref "J1") (pin "CA2") (pinfunction "1_CA2") (pintype "bidirectional"))
    )
    (net (code "90") (name "unconnected-(J1BW-1-PadCB1)") (class "Default")
      (node (ref "J1") (pin "CB1") (pinfunction "1_CB1") (pintype "bidirectional"))
    )
    (net (code "91") (name "unconnected-(J1BX-1-PadCB2)") (class "Default")
      (node (ref "J1") (pin "CB2") (pinfunction "1_CB2") (pintype "bidirectional"))
    )
    (net (code "92") (name "unconnected-(J1C-1-PadAB1)") (class "Default")
      (node (ref "J1") (pin "AB1") (pinfunction "1_AB1") (pintype "bidirectional"))
    )
    (net (code "93") (name "unconnected-(J1CE-1-PadCF1)") (class "Default")
      (node (ref "J1") (pin "CF1") (pinfunction "1_CF1") (pintype "bidirectional"))
    )
    (net (code "94") (name "unconnected-(J1CF-1-PadCF2)") (class "Default")
      (node (ref "J1") (pin "CF2") (pinfunction "1_CF2") (pintype "bidirectional"))
    )
    (net (code "95") (name "unconnected-(J1CY-1-PadCT1)") (class "Default")
      (node (ref "J1") (pin "CT1") (pinfunction "1_CT1") (pintype "bidirectional"))
    )
    (net (code "96") (name "unconnected-(J1D-1-PadAB2)") (class "Default")
      (node (ref "J1") (pin "AB2") (pinfunction "1_AB2") (pintype "bidirectional"))
    )
    (net (code "97") (name "unconnected-(J1DE-1-PadDA1)") (class "Default")
      (node (ref "J1") (pin "DA1") (pinfunction "1_DA1") (pintype "bidirectional"))
    )
    (net (code "98") (name "unconnected-(J1DG-1-PadDB1)") (class "Default")
      (node (ref "J1") (pin "DB1") (pinfunction "1_DB1") (pintype "bidirectional"))
    )
    (net (code "99") (name "unconnected-(J1DH-1-PadDB2)") (class "Default")
      (node (ref "J1") (pin "DB2") (pinfunction "1_DB2") (pintype "bidirectional"))
    )
    (net (code "100") (name "unconnected-(J1DO-1-PadDF1)") (class "Default")
      (node (ref "J1") (pin "DF1") (pinfunction "1_DF1") (pintype "bidirectional"))
    )
    (net (code "101") (name "unconnected-(J1DP-1-PadDF2)") (class "Default")
      (node (ref "J1") (pin "DF2") (pinfunction "1_DF2") (pintype "bidirectional"))
    )
    (net (code "102") (name "unconnected-(J1EA-1-PadDN1)") (class "Default")
      (node (ref "J1") (pin "DN1") (pinfunction "1_DN1") (pintype "bidirectional"))
    )
    (net (code "103") (name "unconnected-(J1K-1-PadAF1)") (class "Default")
      (node (ref "J1") (pin "AF1") (pinfunction "1_AF1") (pintype "bidirectional"))
    )
    (net (code "104") (name "unconnected-(J1L-1-PadAF2)") (class "Default")
      (node (ref "J1") (pin "AF2") (pinfunction "1_AF2") (pintype "bidirectional"))
    )
    (net (code "105") (name "unconnected-(J4-3-PadC)") (class "Default")
      (node (ref "J4") (pin "C") (pinfunction "3_C") (pintype "bidirectional"))
    )
    (net (code "106") (name "unconnected-(J4-4-PadD)") (class "Default")
      (node (ref "J4") (pin "D") (pinfunction "4_D") (pintype "bidirectional"))
    )
    (net (code "107") (name "unconnected-(J4-5-PadE)") (class "Default")
      (node (ref "J4") (pin "E") (pinfunction "5_E") (pintype "bidirectional"))
    )
    (net (code "108") (name "unconnected-(J4-7-PadH)") (class "Default")
      (node (ref "J4") (pin "H") (pinfunction "7_H") (pintype "bidirectional"))
    )
    (net (code "109") (name "unconnected-(J4-9-PadK)") (class "Default")
      (node (ref "J4") (pin "K") (pinfunction "9_K") (pintype "bidirectional"))
    )
    (net (code "110") (name "unconnected-(J4-10-PadL)") (class "Default")
      (node (ref "J4") (pin "L") (pinfunction "10_L") (pintype "bidirectional"))
    )
    (net (code "111") (name "unconnected-(J4-11-PadM)") (class "Default")
      (node (ref "J4") (pin "M") (pinfunction "11_M") (pintype "bidirectional"))
    )
    (net (code "112") (name "unconnected-(J4-12-PadN)") (class "Default")
      (node (ref "J4") (pin "N") (pinfunction "12_N") (pintype "bidirectional"))
    )
    (net (code "113") (name "unconnected-(J4-13-PadP)") (class "Default")
      (node (ref "J4") (pin "P") (pinfunction "13_P") (pintype "bidirectional"))
    )
    (net (code "114") (name "unconnected-(J4-14-PadR)") (class "Default")
      (node (ref "J4") (pin "R") (pinfunction "14_R") (pintype "bidirectional"))
    )
    (net (code "115") (name "unconnected-(J4-15-PadS)") (class "Default")
      (node (ref "J4") (pin "S") (pinfunction "15_S") (pintype "bidirectional"))
    )
    (net (code "116") (name "unconnected-(J4-16-PadT)") (class "Default")
      (node (ref "J4") (pin "T") (pinfunction "16_T") (pintype "bidirectional"))
    )
    (net (code "117") (name "unconnected-(J4-17-PadU)") (class "Default")
      (node (ref "J4") (pin "U") (pinfunction "17_U") (pintype "bidirectional"))
    )
    (net (code "118") (name "unconnected-(J4-18-PadV)") (class "Default")
      (node (ref "J4") (pin "V") (pinfunction "18_V") (pintype "bidirectional"))
    )
    (net (code "119") (name "unconnected-(J4-19-PadW)") (class "Default")
      (node (ref "J4") (pin "W") (pinfunction "19_W") (pintype "bidirectional"))
    )
    (net (code "120") (name "unconnected-(J4-20-PadX)") (class "Default")
      (node (ref "J4") (pin "X") (pinfunction "20_X") (pintype "bidirectional"))
    )
    (net (code "121") (name "unconnected-(J4-21-PadY)") (class "Default")
      (node (ref "J4") (pin "Y") (pinfunction "21_Y") (pintype "bidirectional"))
    )
    (net (code "122") (name "unconnected-(J4-23-PadAA)") (class "Default")
      (node (ref "J4") (pin "AA") (pinfunction "23_AA") (pintype "bidirectional"))
    )
    (net (code "123") (name "unconnected-(J4-24-PadBB)") (class "Default")
      (node (ref "J4") (pin "BB") (pinfunction "24_BB") (pintype "bidirectional"))
    )
    (net (code "124") (name "unconnected-(J4-25-PadCC)") (class "Default")
      (node (ref "J4") (pin "CC") (pinfunction "25_CC") (pintype "bidirectional"))
    )
    (net (code "125") (name "unconnected-(J4-26-PadDD)") (class "Default")
      (node (ref "J4") (pin "DD") (pinfunction "26_DD") (pintype "bidirectional"))
    )
    (net (code "126") (name "unconnected-(J4-27-PadEE)") (class "Default")
      (node (ref "J4") (pin "EE") (pinfunction "27_EE") (pintype "bidirectional"))
    )
    (net (code "127") (name "unconnected-(J4-28-PadFF)") (class "Default")
      (node (ref "J4") (pin "FF") (pinfunction "28_FF") (pintype "bidirectional"))
    )
    (net (code "128") (name "unconnected-(J4-29-PadHH)") (class "Default")
      (node (ref "J4") (pin "HH") (pinfunction "29_HH") (pintype "bidirectional"))
    )
    (net (code "129") (name "unconnected-(J4-30-PadJJ)") (class "Default")
      (node (ref "J4") (pin "JJ") (pinfunction "30_JJ") (pintype "bidirectional"))
    )
    (net (code "130") (name "unconnected-(J4-31-PadKK)") (class "Default")
      (node (ref "J4") (pin "KK") (pinfunction "31_KK") (pintype "bidirectional"))
    )
    (net (code "131") (name "unconnected-(J4-32-PadLL)") (class "Default")
      (node (ref "J4") (pin "LL") (pinfunction "32_LL") (pintype "bidirectional"))
    )
    (net (code "132") (name "unconnected-(J4-33-PadMM)") (class "Default")
      (node (ref "J4") (pin "MM") (pinfunction "33_MM") (pintype "bidirectional"))
    )
    (net (code "133") (name "unconnected-(J4-34-PadNN)") (class "Default")
      (node (ref "J4") (pin "NN") (pinfunction "34_NN") (pintype "bidirectional"))
    )
    (net (code "134") (name "unconnected-(J4-35-PadPP)") (class "Default")
      (node (ref "J4") (pin "PP") (pinfunction "35_PP") (pintype "bidirectional"))
    )
    (net (code "135") (name "unconnected-(J4-36-PadRR)") (class "Default")
      (node (ref "J4") (pin "RR") (pinfunction "36_RR") (pintype "bidirectional"))
    )
    (net (code "136") (name "unconnected-(U2-GPA3-Pad24)") (class "Default")
      (node (ref "U2") (pin "24") (pinfunction "GPA3_24") (pintype "bidirectional"))
    )
    (net (code "137") (name "unconnected-(U2-GPA7-Pad28)") (class "Default")
      (node (ref "U2") (pin "28") (pinfunction "GPA7_28") (pintype "bidirectional"))
    )
    (net (code "138") (name "unconnected-(U2-GPB3-Pad4)") (class "Default")
      (node (ref "U2") (pin "4") (pinfunction "GPB3_4") (pintype "bidirectional"))
    )
    (net (code "139") (name "unconnected-(U2-GPB7-Pad8)") (class "Default")
      (node (ref "U2") (pin "8") (pinfunction "GPB7_8") (pintype "bidirectional"))
    )
    (net (code "140") (name "unconnected-(U2-INTA-Pad20)") (class "Default")
      (node (ref "U2") (pin "20") (pinfunction "INTA_20") (pintype "output"))
    )
    (net (code "141") (name "unconnected-(U2-INTB-Pad19)") (class "Default")
      (node (ref "U2") (pin "19") (pinfunction "INTB_19") (pintype "output"))
    )
    (net (code "142") (name "unconnected-(U7D-O-Pad11)") (class "Default")
      (node (ref "U7") (pin "11") (pinfunction "O_11") (pintype "open_collector"))
    )
    (net (code "143") (name "unconnected-(U10A-T1OUT-Pad14)") (class "Default")
      (node (ref "U10") (pin "14") (pinfunction "T1OUT_14") (pintype "output"))
    )
    (net (code "144") (name "~{BREAK_CYCLE}") (class "Default")
      (node (ref "J1") (pin "BL2") (pinfunction "1_BL2") (pintype "bidirectional"))
    )
    (net (code "145") (name "~{BRK_DATA}") (class "Default")
      (node (ref "J1") (pin "BK2") (pinfunction "1_BK2") (pintype "bidirectional"))
      (node (ref "U7") (pin "3") (pinfunction "O_3") (pintype "open_collector"))
    )
    (net (code "146") (name "~{BRK_IN_PROG}") (class "Default")
      (node (ref "J1") (pin "BE2") (pinfunction "1_BE2") (pintype "bidirectional"))
    )
    (net (code "147") (name "~{BUS_STROBE}") (class "Default")
      (node (ref "J1") (pin "CK1") (pinfunction "1_CK1") (pintype "bidirectional"))
    )
    (net (code "148") (name "~{C0}") (class "Default")
      (node (ref "J1") (pin "CE1") (pinfunction "1_CE1") (pintype "bidirectional"))
    )
    (net (code "149") (name "~{C1}") (class "Default")
      (node (ref "J1") (pin "CH1") (pinfunction "1_CH1") (pintype "bidirectional"))
    )
    (net (code "150") (name "~{C2}") (class "Default")
      (node (ref "J1") (pin "CJ1") (pinfunction "1_CJ1") (pintype "bidirectional"))
    )
    (net (code "151") (name "~{CPMA_DISABLE}") (class "Default")
      (node (ref "J1") (pin "CU1") (pinfunction "1_CU1") (pintype "bidirectional"))
    )
    (net (code "152") (name "~{DATA00}") (class "Default")
      (node (ref "J1") (pin "AR1") (pinfunction "1_AR1") (pintype "bidirectional"))
      (node (ref "U3") (pin "3") (pinfunction "O_3") (pintype "open_collector"))
    )
    (net (code "153") (name "~{DATA01}") (class "Default")
      (node (ref "J1") (pin "AS1") (pinfunction "1_AS1") (pintype "bidirectional"))
      (node (ref "U3") (pin "6") (pinfunction "O_6") (pintype "open_collector"))
    )
    (net (code "154") (name "~{DATA02}") (class "Default")
      (node (ref "J1") (pin "AU1") (pinfunction "1_AU1") (pintype "bidirectional"))
      (node (ref "U3") (pin "8") (pinfunction "O_8") (pintype "open_collector"))
    )
    (net (code "155") (name "~{DATA03}") (class "Default")
      (node (ref "J1") (pin "AV1") (pinfunction "1_AV1") (pintype "bidirectional"))
      (node (ref "U3") (pin "11") (pinfunction "O_11") (pintype "open_collector"))
    )
    (net (code "156") (name "~{DATA04}") (class "Default")
      (node (ref "J1") (pin "BR1") (pinfunction "1_BR1") (pintype "bidirectional"))
      (node (ref "U4") (pin "3") (pinfunction "O_3") (pintype "open_collector"))
    )
    (net (code "157") (name "~{DATA05}") (class "Default")
      (node (ref "J1") (pin "BS1") (pinfunction "1_BS1") (pintype "bidirectional"))
      (node (ref "U4") (pin "6") (pinfunction "O_6") (pintype "open_collector"))
    )
    (net (code "158") (name "~{DATA06}") (class "Default")
      (node (ref "J1") (pin "BU1") (pinfunction "1_BU1") (pintype "bidirectional"))
      (node (ref "U4") (pin "8") (pinfunction "O_8") (pintype "open_collector"))
    )
    (net (code "159") (name "~{DATA07}") (class "Default")
      (node (ref "J1") (pin "BV1") (pinfunction "1_BV1") (pintype "bidirectional"))
      (node (ref "U4") (pin "11") (pinfunction "O_11") (pintype "open_collector"))
    )
    (net (code "160") (name "~{DATA08}") (class "Default")
      (node (ref "J1") (pin "DR1") (pinfunction "1_DR1") (pintype "bidirectional"))
      (node (ref "U5") (pin "3") (pinfunction "O_3") (pintype "open_collector"))
    )
    (net (code "161") (name "~{DATA09}") (class "Default")
      (node (ref "J1") (pin "DS1") (pinfunction "1_DS1") (pintype "bidirectional"))
      (node (ref "U5") (pin "6") (pinfunction "O_6") (pintype "open_collector"))
    )
    (net (code "162") (name "~{DATA10}") (class "Default")
      (node (ref "J1") (pin "DU1") (pinfunction "1_DU1") (pintype "bidirectional"))
      (node (ref "U5") (pin "8") (pinfunction "O_8") (pintype "open_collector"))
    )
    (net (code "163") (name "~{DATA11}") (class "Default")
      (node (ref "J1") (pin "DV1") (pinfunction "1_DV1") (pintype "bidirectional"))
      (node (ref "U5") (pin "11") (pinfunction "O_11") (pintype "open_collector"))
    )
    (net (code "164") (name "~{D}") (class "Default")
      (node (ref "J1") (pin "DK2") (pinfunction "1_DK2") (pintype "bidirectional"))
    )
    (net (code "165") (name "~{EMA0}") (class "Default")
      (node (ref "J1") (pin "AD2") (pinfunction "1_AD2") (pintype "bidirectional"))
    )
    (net (code "166") (name "~{EMA1}") (class "Default")
      (node (ref "J1") (pin "AE2") (pinfunction "1_AE2") (pintype "bidirectional"))
    )
    (net (code "167") (name "~{EMA2}") (class "Default")
      (node (ref "J1") (pin "AH2") (pinfunction "1_AH2") (pintype "bidirectional"))
    )
    (net (code "168") (name "~{E}") (class "Default")
      (node (ref "J1") (pin "DL2") (pinfunction "1_DL2") (pintype "bidirectional"))
    )
    (net (code "169") (name "~{FSET}") (class "Default")
      (node (ref "J1") (pin "DP2") (pinfunction "1_DP2") (pintype "bidirectional"))
    )
    (net (code "170") (name "~{F}") (class "Default")
      (node (ref "J1") (pin "DJ2") (pinfunction "1_DJ2") (pintype "bidirectional"))
    )
    (net (code "171") (name "~{IND1}") (class "Default")
      (node (ref "J1") (pin "CU2") (pinfunction "1_CU2") (pintype "bidirectional"))
    )
    (net (code "172") (name "~{IND2}") (class "Default")
      (node (ref "J1") (pin "CV2") (pinfunction "1_CV2") (pintype "bidirectional"))
    )
    (net (code "173") (name "~{INTERNAL_IO}") (class "Default")
      (node (ref "J1") (pin "CL1") (pinfunction "1_CL1") (pintype "bidirectional"))
    )
    (net (code "174") (name "~{INT_RQST}") (class "Default")
      (node (ref "J1") (pin "CP1") (pinfunction "1_CP1") (pintype "bidirectional"))
    )
    (net (code "175") (name "~{IO_PAUSE}") (class "Default")
      (node (ref "J1") (pin "CD1") (pinfunction "1_CD1") (pintype "bidirectional"))
    )
    (net (code "176") (name "~{IR0}") (class "Default")
      (node (ref "J1") (pin "DD2") (pinfunction "1_DD2") (pintype "bidirectional"))
    )
    (net (code "177") (name "~{IR1}") (class "Default")
      (node (ref "J1") (pin "DE2") (pinfunction "1_DE2") (pintype "bidirectional"))
    )
    (net (code "178") (name "~{IR2}") (class "Default")
      (node (ref "J1") (pin "DH2") (pinfunction "1_DH2") (pintype "bidirectional"))
    )
    (net (code "179") (name "~{KEY_CONT}") (class "Default")
      (node (ref "J1") (pin "DU2") (pinfunction "1_DU2") (pintype "bidirectional"))
      (node (ref "U6") (pin "11") (pinfunction "O_11") (pintype "open_collector"))
    )
    (net (code "180") (name "~{LA_ENABLE}") (class "Default")
      (node (ref "J1") (pin "BM2") (pinfunction "1_BM2") (pintype "bidirectional"))
      (node (ref "U6") (pin "6") (pinfunction "O_6") (pintype "open_collector"))
    )
    (net (code "181") (name "~{LINK_DATA}") (class "Default")
      (node (ref "J1") (pin "CR2") (pinfunction "1_CR2") (pintype "bidirectional"))
    )
    (net (code "182") (name "~{LINK_LOAD}") (class "Default")
      (node (ref "J1") (pin "CS2") (pinfunction "1_CS2") (pintype "bidirectional"))
    )
    (net (code "183") (name "~{LINK}") (class "Default")
      (node (ref "J1") (pin "AV2") (pinfunction "1_AV2") (pintype "bidirectional"))
    )
    (net (code "184") (name "~{LOAD_CONT}") (class "Default")
      (node (ref "J1") (pin "BH2") (pinfunction "1_BH2") (pintype "bidirectional"))
    )
    (net (code "185") (name "~{MA00}") (class "Default")
      (node (ref "J1") (pin "AD1") (pinfunction "1_AD1") (pintype "bidirectional"))
    )
    (net (code "186") (name "~{MA01}") (class "Default")
      (node (ref "J1") (pin "AE1") (pinfunction "1_AE1") (pintype "bidirectional"))
    )
    (net (code "187") (name "~{MA02}") (class "Default")
      (node (ref "J1") (pin "AH1") (pinfunction "1_AH1") (pintype "bidirectional"))
    )
    (net (code "188") (name "~{MA03}") (class "Default")
      (node (ref "J1") (pin "AJ1") (pinfunction "1_AJ1") (pintype "bidirectional"))
    )
    (net (code "189") (name "~{MA04}") (class "Default")
      (node (ref "J1") (pin "BD1") (pinfunction "1_BD1") (pintype "bidirectional"))
    )
    (net (code "190") (name "~{MA05}") (class "Default")
      (node (ref "J1") (pin "BE1") (pinfunction "1_BE1") (pintype "bidirectional"))
    )
    (net (code "191") (name "~{MA06}") (class "Default")
      (node (ref "J1") (pin "BH1") (pinfunction "1_BH1") (pintype "bidirectional"))
    )
    (net (code "192") (name "~{MA07}") (class "Default")
      (node (ref "J1") (pin "BJ1") (pinfunction "1_BJ1") (pintype "bidirectional"))
    )
    (net (code "193") (name "~{MA08}") (class "Default")
      (node (ref "J1") (pin "DD1") (pinfunction "1_DD1") (pintype "bidirectional"))
    )
    (net (code "194") (name "~{MA09}") (class "Default")
      (node (ref "J1") (pin "DE1") (pinfunction "1_DE1") (pintype "bidirectional"))
    )
    (net (code "195") (name "~{MA10}") (class "Default")
      (node (ref "J1") (pin "DH1") (pinfunction "1_DH1") (pintype "bidirectional"))
    )
    (net (code "196") (name "~{MA11}") (class "Default")
      (node (ref "J1") (pin "DJ1") (pinfunction "1_DJ1") (pintype "bidirectional"))
    )
    (net (code "197") (name "~{MD00}") (class "Default")
      (node (ref "J1") (pin "AK1") (pinfunction "1_AK1") (pintype "bidirectional"))
    )
    (net (code "198") (name "~{MD01}") (class "Default")
      (node (ref "J1") (pin "AL1") (pinfunction "1_AL1") (pintype "bidirectional"))
    )
    (net (code "199") (name "~{MD02}") (class "Default")
      (node (ref "J1") (pin "AM1") (pinfunction "1_AM1") (pintype "bidirectional"))
    )
    (net (code "200") (name "~{MD03}") (class "Default")
      (node (ref "J1") (pin "AP1") (pinfunction "1_AP1") (pintype "bidirectional"))
    )
    (net (code "201") (name "~{MD04}") (class "Default")
      (node (ref "J1") (pin "BK1") (pinfunction "1_BK1") (pintype "bidirectional"))
    )
    (net (code "202") (name "~{MD05}") (class "Default")
      (node (ref "J1") (pin "BL1") (pinfunction "1_BL1") (pintype "bidirectional"))
    )
    (net (code "203") (name "~{MD06}") (class "Default")
      (node (ref "J1") (pin "BM1") (pinfunction "1_BM1") (pintype "bidirectional"))
    )
    (net (code "204") (name "~{MD07}") (class "Default")
      (node (ref "J1") (pin "BP1") (pinfunction "1_BP1") (pintype "bidirectional"))
    )
    (net (code "205") (name "~{MD08}") (class "Default")
      (node (ref "J1") (pin "DK1") (pinfunction "1_DK1") (pintype "bidirectional"))
    )
    (net (code "206") (name "~{MD09}") (class "Default")
      (node (ref "J1") (pin "DL1") (pinfunction "1_DL1") (pintype "bidirectional"))
    )
    (net (code "207") (name "~{MD10}") (class "Default")
      (node (ref "J1") (pin "DM1") (pinfunction "1_DM1") (pintype "bidirectional"))
    )
    (net (code "208") (name "~{MD11}") (class "Default")
      (node (ref "J1") (pin "DP1") (pinfunction "1_DP1") (pintype "bidirectional"))
    )
    (net (code "209") (name "~{MD_DIR}") (class "Default")
      (node (ref "J1") (pin "AK2") (pinfunction "1_AK2") (pintype "bidirectional"))
      (node (ref "U7") (pin "6") (pinfunction "O_6") (pintype "open_collector"))
    )
    (net (code "210") (name "~{MEM_START}") (class "Default")
      (node (ref "J1") (pin "AJ2") (pinfunction "1_AJ2") (pintype "bidirectional"))
      (node (ref "U6") (pin "3") (pinfunction "O_3") (pintype "open_collector"))
    )
    (net (code "211") (name "~{MS_DISABLE}") (class "Default")
      (node (ref "J1") (pin "CV1") (pinfunction "1_CV1") (pintype "bidirectional"))
      (node (ref "U6") (pin "8") (pinfunction "O_8") (pintype "open_collector"))
    )
    (net (code "212") (name "~{NOT_LAST_TR}") (class "Default")
      (node (ref "J1") (pin "CM1") (pinfunction "1_CM1") (pintype "bidirectional"))
    )
    (net (code "213") (name "~{NTS_STALL}") (class "Default")
      (node (ref "J1") (pin "BR2") (pinfunction "1_BR2") (pintype "bidirectional"))
    )
    (net (code "214") (name "~{OVERFLOW}") (class "Default")
      (node (ref "J1") (pin "BJ2") (pinfunction "1_BJ2") (pintype "bidirectional"))
    )
    (net (code "215") (name "~{RESET}") (class "Default")
      (node (ref "C11") (pin "1") (pinfunction "1_1") (pintype "passive"))
      (node (ref "D1") (pin "A") (pinfunction "A_A") (pintype "passive"))
      (node (ref "J3") (pin "5") (pinfunction "5_5") (pintype "passive"))
      (node (ref "R19") (pin "1") (pinfunction "1_1") (pintype "passive"))
      (node (ref "U1") (pin "1") (pinfunction "PC6(/RESET)_1") (pintype "bidirectional"))
    )
    (net (code "216") (name "~{ROM_ADDR}") (class "Default")
      (node (ref "J1") (pin "AU2") (pinfunction "1_AU2") (pintype "bidirectional"))
    )
    (net (code "217") (name "~{RUN}") (class "Default")
      (node (ref "J1") (pin "BU2") (pinfunction "1_BU2") (pintype "bidirectional"))
      (node (ref "R2") (pin "2") (pinfunction "2_2") (pintype "passive"))
    )
    (net (code "218") (name "~{SKIP}") (class "Default")
      (node (ref "J1") (pin "CS1") (pinfunction "1_CS1") (pintype "bidirectional"))
    )
    (net (code "219") (name "~{STOP}") (class "Default")
      (node (ref "J1") (pin "DS2") (pinfunction "1_DS2") (pintype "bidirectional"))
      (node (ref "U7") (pin "8") (pinfunction "O_8") (pintype "open_collector"))
    )
    (net (code "220") (name "~{TS1}") (class "Default")
      (node (ref "J1") (pin "CK2") (pinfunction "1_CK2") (pintype "bidirectional"))
    )
    (net (code "221") (name "~{TS2}") (class "Default")
      (node (ref "J1") (pin "CL2") (pinfunction "1_CL2") (pintype "bidirectional"))
    )
    (net (code "222") (name "~{TS3}") (class "Default")
      (node (ref "J1") (pin "CM2") (pinfunction "1_CM2") (pintype "bidirectional"))
    )
    (net (code "223") (name "~{TS4}") (class "Default")
      (node (ref "J1") (pin "CP2") (pinfunction "1_CP2") (pintype "bidirectional"))
      (node (ref "U8") (pin "13") (pinfunction "I2_13") (pintype "input"))
    )
    (net (code "224") (name "~{USER_MODE}") (class "Default")
      (node (ref "J1") (pin "DM2") (pinfunction "1_DM2") (pintype "bidirectional"))
    )
    (net (code "225") (name "~{W_KEY_CONTROL}") (class "Default")
      (node (ref "U1") (pin "13") (pinfunction "PD7(AIN1)_13") (pintype "bidirectional"))
      (node (ref "U6") (pin "12") (pinfunction "I0_12") (pintype "input"))
    )
    (net (code "226") (name "~{W_LA_ENABLE}") (class "Default")
      (node (ref "U1") (pin "11") (pinfunction "PD5(T1)_11") (pintype "bidirectional"))
      (node (ref "U6") (pin "4") (pinfunction "I0_4") (pintype "input"))
    )
    (net (code "227") (name "~{W_MEM_START}") (class "Default")
      (node (ref "R7") (pin "2") (pinfunction "2_2") (pintype "passive"))
      (node (ref "U1") (pin "25") (pinfunction "PC2(ADC2)_25") (pintype "bidirectional"))
      (node (ref "U6") (pin "1") (pinfunction "I0_1") (pintype "input"))
      (node (ref "U6") (pin "2") (pinfunction "I1_2") (pintype "input"))
    )
    (net (code "228") (name "~{W_MS_IR_DISABLE}") (class "Default")
      (node (ref "U1") (pin "12") (pinfunction "PD6(AIN0)_12") (pintype "bidirectional"))
      (node (ref "U6") (pin "9") (pinfunction "I0_9") (pintype "input"))
    )
  )
)
